# 01_Top.net
KiCad netlist of a schematic drawn in Altium Designer
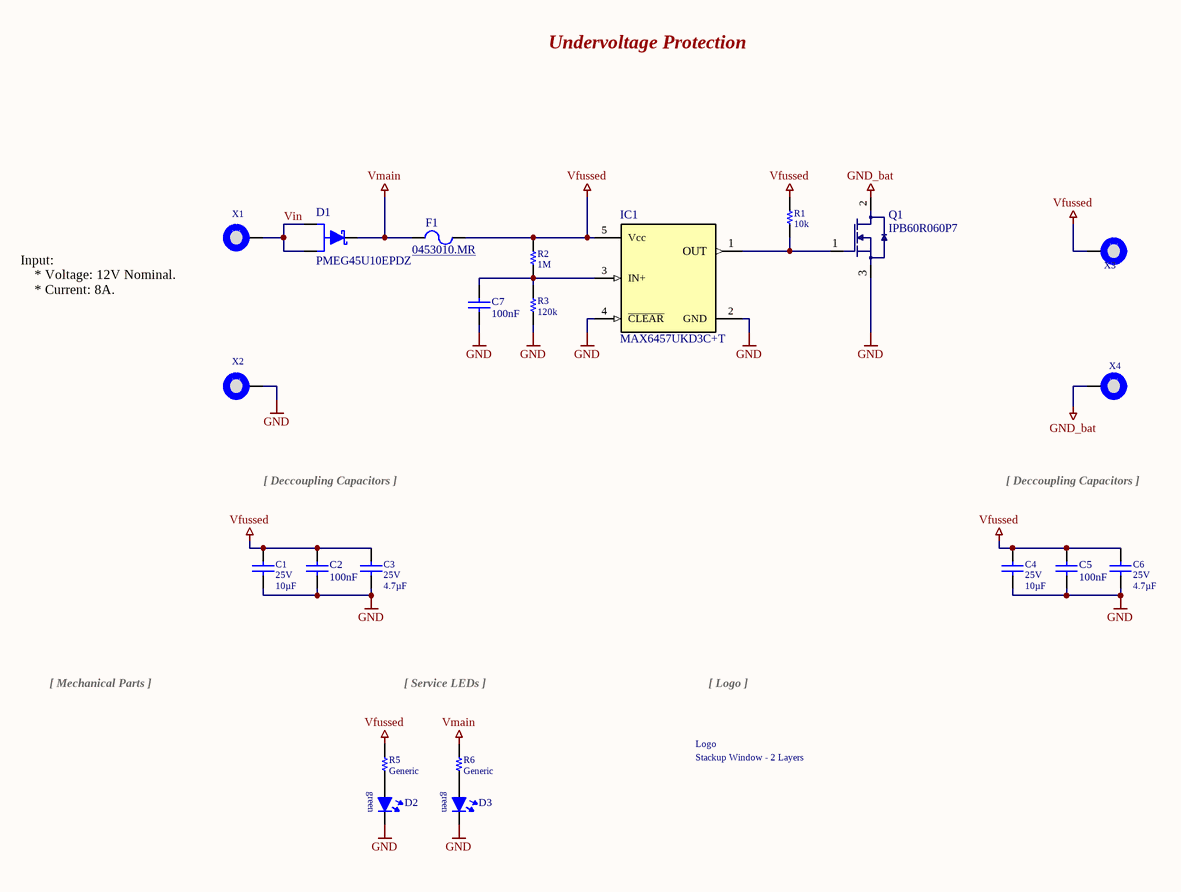
[diagram p0: [01] Top.SchDoc]

(export (version "E")
  (design (tool "Eeschema 10.0.6"))
  (components
    (comp (ref "A1")
      (value "Logo_Mehdi")
      (footprint "LOGO_MEHDI")
      (description "Logo Mehdi")
      (libsource (lib "GA_Misc") (part "Logo_Mehdi"))
    )
    (comp (ref "A2")
      (value "Stackup Window - 2 Layers")
      (footprint "LAYER_WINDOW_2_LAYERS")
      (description "Layer Stackup Window for 2 Layers (Top, Bottom)")
      (libsource (lib "GA_Misc") (part "Stackup Window - 2 Layers"))
    )
    (comp (ref "C1")
      (value "10µF")
      (footprint "CAPC1210(3225)280_N")
      (description "Capacitor")
      (fields
        (field (name "EXACTPARTNUMBER") "no")
        (field (name "TOLERANCE") "20%")
        (field (name "VOLTAGE") "25V")
        (field (name "DESIGNEDBY") "Wilhelm Stellmach")
        (field (name "PUBLISHER") "General Acoustics e.K")
      )
      (libsource (lib "GA_Passives2") (part "CAP-X7R_1210_25V_10uF"))
    )
    (comp (ref "C2")
      (value "100nF")
      (footprint "CAPC0603(1608)100_N")
      (description "Capacitor")
      (fields
        (field (name "EXACTPARTNUMBER") "no")
        (field (name "TOLERANCE") "10%")
        (field (name "DESIGNEDBY") "Wilhelm Stellmach")
        (field (name "PUBLISHER") "General Acoustics e.K")
      )
      (libsource (lib "GA_Passives2") (part "CAP-X7R_0603_50V_Generic"))
    )
    (comp (ref "C3")
      (value "4.7µF")
      (footprint "CAPC3225X20N")
      (description "Capacitor")
      (fields
        (field (name "EXACTPARTNUMBER") "no")
        (field (name "TOLERANCE") "10%")
        (field (name "VOLTAGE") "25V")
        (field (name "DESIGNEDBY") "Wilhelm Stellmach")
        (field (name "PUBLISHER") "General Acoustics e.K")
      )
      (libsource (lib "GA_Passives2") (part "CAP-X7R_1210_25V_4.7uF"))
    )
    (comp (ref "C4")
      (value "10µF")
      (footprint "CAPC1210(3225)280_N")
      (description "Capacitor")
      (fields
        (field (name "EXACTPARTNUMBER") "no")
        (field (name "TOLERANCE") "20%")
        (field (name "VOLTAGE") "25V")
        (field (name "DESIGNEDBY") "Wilhelm Stellmach")
        (field (name "PUBLISHER") "General Acoustics e.K")
      )
      (libsource (lib "GA_Passives2") (part "CAP-X7R_1210_25V_10uF"))
    )
    (comp (ref "C5")
      (value "100nF")
      (footprint "CAPC0603(1608)100_N")
      (description "Capacitor")
      (fields
        (field (name "EXACTPARTNUMBER") "no")
        (field (name "TOLERANCE") "10%")
        (field (name "DESIGNEDBY") "Wilhelm Stellmach")
        (field (name "PUBLISHER") "General Acoustics e.K")
      )
      (libsource (lib "GA_Passives2") (part "CAP-X7R_0603_50V_Generic"))
    )
    (comp (ref "C6")
      (value "4.7µF")
      (footprint "CAPC3225X20N")
      (description "Capacitor")
      (fields
        (field (name "EXACTPARTNUMBER") "no")
        (field (name "TOLERANCE") "10%")
        (field (name "VOLTAGE") "25V")
        (field (name "DESIGNEDBY") "Wilhelm Stellmach")
        (field (name "PUBLISHER") "General Acoustics e.K")
      )
      (libsource (lib "GA_Passives2") (part "CAP-X7R_1210_25V_4.7uF"))
    )
    (comp (ref "C7")
      (value "100nF")
      (footprint "CAPC0603(1608)100_N")
      (description "Capacitor")
      (fields
        (field (name "EXACTPARTNUMBER") "no")
        (field (name "TOLERANCE") "10%")
        (field (name "DESIGNEDBY") "Wilhelm Stellmach")
        (field (name "PUBLISHER") "General Acoustics e.K")
      )
      (libsource (lib "GA_Passives2") (part "CAP-X7R_0603_50V_Generic"))
    )
    (comp (ref "D1")
      (value "PMEG45U10EPDZ")
      (footprint "DPAK213P650X82-3N")
      (description "Shottky, 45 V, 10 A extremely low Vf barrier rectifier")
      (fields
        (field (name "MANUFACTURER PART NUMBER 1") "PMEG45U10EPDZ")
        (field (name "PUBLISHER") "Mehdi El Korch")
        (field (name "DESIGNEDBY") "Mehdi EL Korch")
      )
      (libsource (lib "GA_Diodes2") (part "PMEG45U10EPDZ"))
    )
    (comp (ref "D2")
      (value "LG L29K-G2J1-24-Z")
      (footprint "SODFL170X85-2N")
      (description "LED green 570nm, 4lm/W, 2.2...5.6mcd at 2mA, 3.4mW SmartLED")
      (fields
        (field (name "EXACTPARTNUMBER") "yes")
        (field (name "MANUFACTURER") "OSRAM Opto Semiconductors")
        (field (name "DESIGNEDBY") "Marcus Schoeling")
        (field (name "PUBLISHER") "General Acoustics")
      )
      (libsource (lib "GA_Diodes2") (part "LG L29K-G2J1-24-Z"))
    )
    (comp (ref "D3")
      (value "LG L29K-G2J1-24-Z")
      (footprint "SODFL170X85-2N")
      (description "LED green 570nm, 4lm/W, 2.2...5.6mcd at 2mA, 3.4mW SmartLED")
      (fields
        (field (name "EXACTPARTNUMBER") "yes")
        (field (name "MANUFACTURER") "OSRAM Opto Semiconductors")
        (field (name "DESIGNEDBY") "Marcus Schoeling")
        (field (name "PUBLISHER") "General Acoustics")
      )
      (libsource (lib "GA_Diodes2") (part "LG L29K-G2J1-24-Z"))
    )
    (comp (ref "F1")
      (value "0453010.MR")
      (footprint "6.10x2.69mm")
      (description "Fuse Chip Very Fast Acting 10A 125V SMD Solder Pad 2410 Ceramic T/R Automotive CE/CSA/PSE/UL")
      (fields
        (field (name "MANUFACTURER PART NUMBER 1") "0453010.MR")
        (field (name "PUBLISHER") "Mehdi El Korch")
        (field (name "DESIGNEDBY") "Mehdi El Korch")
      )
      (libsource (lib "GA_Passives2") (part "0453010.MR"))
    )
    (comp (ref "IC1")
      (value "MAX6457UKD3C+T")
      (footprint "SOT95P280X125-5N")
      (description "Volt Supervisor Monitor 4V to 28V 5-Pin SOT-23 T/R")
      (fields
        (field (name "MANUFACTURER PART NUMBER 1") "MAX6457UKD3C+T")
        (field (name "PUBLISHER") "Mehdi EL Korch")
        (field (name "DESIGNEDBY") "Mehdi EL korch")
      )
      (libsource (lib "GA_GateDriver2") (part "MAX6457UKD3C+T"))
    )
    (comp (ref "Q1")
      (value "IPB60R060P7")
      (footprint "TO263-3")
      (description "MOSFET, N-CH, 600V, 48A, 151A Pulse, 50mOhm, Qg 67nC")
      (fields
        (field (name "EXACTPARTNUMBER") "yes")
        (field (name "MANUFACTURER") "Infineon")
        (field (name "MANUFACTURERPARTNUMBER") "IPB60R060P7")
        (field (name "DESIGNEDBY") "Wilhelm Stellmach")
        (field (name "PUBLISHER") "General Acoustics")
      )
      (libsource (lib "GA_Transisotrs2") (part "IPB60R060P7"))
    )
    (comp (ref "R1")
      (value "10k")
      (footprint "RESC0603(1608)_N")
      (description "Resistor")
      (fields
        (field (name "EXACTPARTNUMBER") "no")
        (field (name "TOLERANCE") "1%")
        (field (name "DESIGNEDBY") "Wilhelm Stellmach")
        (field (name "PUBLISHER") "General Acoustics e.K")
      )
      (libsource (lib "") (part "RES-0603_Generic_1"))
    )
    (comp (ref "R2")
      (value "1M")
      (footprint "RESC0603(1608)_N")
      (description "Resistor")
      (fields
        (field (name "EXACTPARTNUMBER") "no")
        (field (name "TOLERANCE") "1%")
        (field (name "DESIGNEDBY") "Wilhelm Stellmach")
        (field (name "PUBLISHER") "General Acoustics e.K")
      )
      (libsource (lib "") (part "RES-0603_Generic_1"))
    )
    (comp (ref "R3")
      (value "120k")
      (footprint "RESC0603(1608)_N")
      (description "Resistor")
      (fields
        (field (name "EXACTPARTNUMBER") "no")
        (field (name "TOLERANCE") "1%")
        (field (name "DESIGNEDBY") "Wilhelm Stellmach")
        (field (name "PUBLISHER") "General Acoustics e.K")
      )
      (libsource (lib "GA_Passives2") (part "RES-0603_Generic"))
    )
    (comp (ref "R5")
      (value "Generic")
      (footprint "RESC0603(1608)_N")
      (description "Resistor")
      (fields
        (field (name "EXACTPARTNUMBER") "no")
        (field (name "TOLERANCE") "1%")
        (field (name "DESIGNEDBY") "Wilhelm Stellmach")
        (field (name "PUBLISHER") "General Acoustics e.K")
      )
      (libsource (lib "GA_Passives2") (part "RES-0603_Generic"))
    )
    (comp (ref "R6")
      (value "Generic")
      (footprint "RESC0603(1608)_N")
      (description "Resistor")
      (fields
        (field (name "EXACTPARTNUMBER") "no")
        (field (name "TOLERANCE") "1%")
        (field (name "DESIGNEDBY") "Wilhelm Stellmach")
        (field (name "PUBLISHER") "General Acoustics e.K")
      )
      (libsource (lib "GA_Passives2") (part "RES-0603_Generic"))
    )
    (comp (ref "X1")
      (value "SolderPad_6/3.2")
      (footprint "SPAD_6/3.2")
      (description "Solder Pad, 6mm copper, 3.2mm hole")
      (fields
        (field (name "EXACTPARTNUMBER") "no")
        (field (name "MANUFACTURERPARTNUMBER") "6/3.2")
        (field (name "DESIGNEDBY") "Wilhelm Stellmach")
        (field (name "PUBLISHER") "General Acoustics e.K.")
      )
      (libsource (lib "GA_Connectors2") (part "SolderPad_6/3.2"))
    )
    (comp (ref "X2")
      (value "SolderPad_6/3.2")
      (footprint "SPAD_6/3.2")
      (description "Solder Pad, 6mm copper, 3.2mm hole")
      (fields
        (field (name "EXACTPARTNUMBER") "no")
        (field (name "MANUFACTURERPARTNUMBER") "6/3.2")
        (field (name "DESIGNEDBY") "Wilhelm Stellmach")
        (field (name "PUBLISHER") "General Acoustics e.K.")
      )
      (libsource (lib "GA_Connectors2") (part "SolderPad_6/3.2"))
    )
    (comp (ref "X3")
      (value "SolderPad_6/3.2")
      (footprint "SPAD_6/3.2")
      (description "Solder Pad, 6mm copper, 3.2mm hole")
      (fields
        (field (name "EXACTPARTNUMBER") "no")
        (field (name "MANUFACTURERPARTNUMBER") "6/3.2")
        (field (name "DESIGNEDBY") "Wilhelm Stellmach")
        (field (name "PUBLISHER") "General Acoustics e.K.")
      )
      (libsource (lib "GA_Connectors2") (part "SolderPad_6/3.2"))
    )
    (comp (ref "X4")
      (value "SolderPad_6/3.2")
      (footprint "SPAD_6/3.2")
      (description "Solder Pad, 6mm copper, 3.2mm hole")
      (fields
        (field (name "EXACTPARTNUMBER") "no")
        (field (name "MANUFACTURERPARTNUMBER") "6/3.2")
        (field (name "DESIGNEDBY") "Wilhelm Stellmach")
        (field (name "PUBLISHER") "General Acoustics e.K.")
      )
      (libsource (lib "GA_Connectors2") (part "SolderPad_6/3.2"))
    )
  )
  (nets
    (net (code "1") (name "/Vin") (class "Default")
      (node (ref "D1") (pin "1") (pinfunction "A_1") (pintype "passive"))
      (node (ref "D1") (pin "2") (pinfunction "A_2") (pintype "passive"))
      (node (ref "X1") (pin "1") (pinfunction "1_1") (pintype "passive"))
    )
    (net (code "2") (name "GND") (class "Default")
      (node (ref "C1") (pin "1") (pinfunction "1_1") (pintype "passive"))
      (node (ref "C2") (pin "1") (pinfunction "1_1") (pintype "passive"))
      (node (ref "C3") (pin "1") (pinfunction "1_1") (pintype "passive"))
      (node (ref "C4") (pin "1") (pinfunction "1_1") (pintype "passive"))
      (node (ref "C5") (pin "1") (pinfunction "1_1") (pintype "passive"))
      (node (ref "C6") (pin "1") (pinfunction "1_1") (pintype "passive"))
      (node (ref "C7") (pin "1") (pinfunction "1_1") (pintype "passive"))
      (node (ref "D2") (pin "1") (pinfunction "K_1") (pintype "passive"))
      (node (ref "D3") (pin "1") (pinfunction "K_1") (pintype "passive"))
      (node (ref "IC1") (pin "2") (pinfunction "GND_2") (pintype "power_in"))
      (node (ref "IC1") (pin "4") (pinfunction "~{CLEAR}_4") (pintype "input"))
      (node (ref "Q1") (pin "3") (pinfunction "S_3") (pintype "passive"))
      (node (ref "R3") (pin "1") (pinfunction "1_1") (pintype "passive"))
      (node (ref "X2") (pin "1") (pinfunction "1_1") (pintype "passive"))
    )
    (net (code "3") (name "GND_bat") (class "Default")
      (node (ref "Q1") (pin "2") (pinfunction "D_2") (pintype "passive"))
      (node (ref "X4") (pin "1") (pinfunction "1_1") (pintype "passive"))
    )
    (net (code "4") (name "Net-(D2-A)") (class "Default")
      (node (ref "D2") (pin "2") (pinfunction "A_2") (pintype "passive"))
      (node (ref "R5") (pin "1") (pinfunction "1_1") (pintype "passive"))
    )
    (net (code "5") (name "Net-(D3-A)") (class "Default")
      (node (ref "D3") (pin "2") (pinfunction "A_2") (pintype "passive"))
      (node (ref "R6") (pin "1") (pinfunction "1_1") (pintype "passive"))
    )
    (net (code "6") (name "Net-(IC1-IN+)") (class "Default")
      (node (ref "C7") (pin "2") (pinfunction "2_2") (pintype "passive"))
      (node (ref "IC1") (pin "3") (pinfunction "IN+_3") (pintype "input"))
      (node (ref "R2") (pin "2") (pinfunction "2_2") (pintype "passive"))
      (node (ref "R3") (pin "2") (pinfunction "2_2") (pintype "passive"))
    )
    (net (code "7") (name "Net-(IC1-OUT)") (class "Default")
      (node (ref "IC1") (pin "1") (pinfunction "OUT_1") (pintype "output"))
      (node (ref "Q1") (pin "1") (pinfunction "G_1") (pintype "passive"))
      (node (ref "R1") (pin "2") (pinfunction "2_2") (pintype "passive"))
    )
    (net (code "8") (name "Vfussed") (class "Default")
      (node (ref "C1") (pin "2") (pinfunction "2_2") (pintype "passive"))
      (node (ref "C2") (pin "2") (pinfunction "2_2") (pintype "passive"))
      (node (ref "C3") (pin "2") (pinfunction "2_2") (pintype "passive"))
      (node (ref "C4") (pin "2") (pinfunction "2_2") (pintype "passive"))
      (node (ref "C5") (pin "2") (pinfunction "2_2") (pintype "passive"))
      (node (ref "C6") (pin "2") (pinfunction "2_2") (pintype "passive"))
      (node (ref "F1") (pin "2") (pinfunction "2_2") (pintype "passive"))
      (node (ref "IC1") (pin "5") (pinfunction "Vcc_5") (pintype "power_in"))
      (node (ref "R1") (pin "1") (pinfunction "1_1") (pintype "passive"))
      (node (ref "R2") (pin "1") (pinfunction "1_1") (pintype "passive"))
      (node (ref "R5") (pin "2") (pinfunction "2_2") (pintype "passive"))
      (node (ref "X3") (pin "1") (pinfunction "1_1") (pintype "passive"))
    )
    (net (code "9") (name "Vmain") (class "Default")
      (node (ref "D1") (pin "3") (pinfunction "K_3") (pintype "passive"))
      (node (ref "F1") (pin "1") (pinfunction "1_1") (pintype "passive"))
      (node (ref "R6") (pin "2") (pinfunction "2_2") (pintype "passive"))
    )
  )
)
